# BOC_PWR.net
KiCad netlist of a schematic drawn in Altium Designer
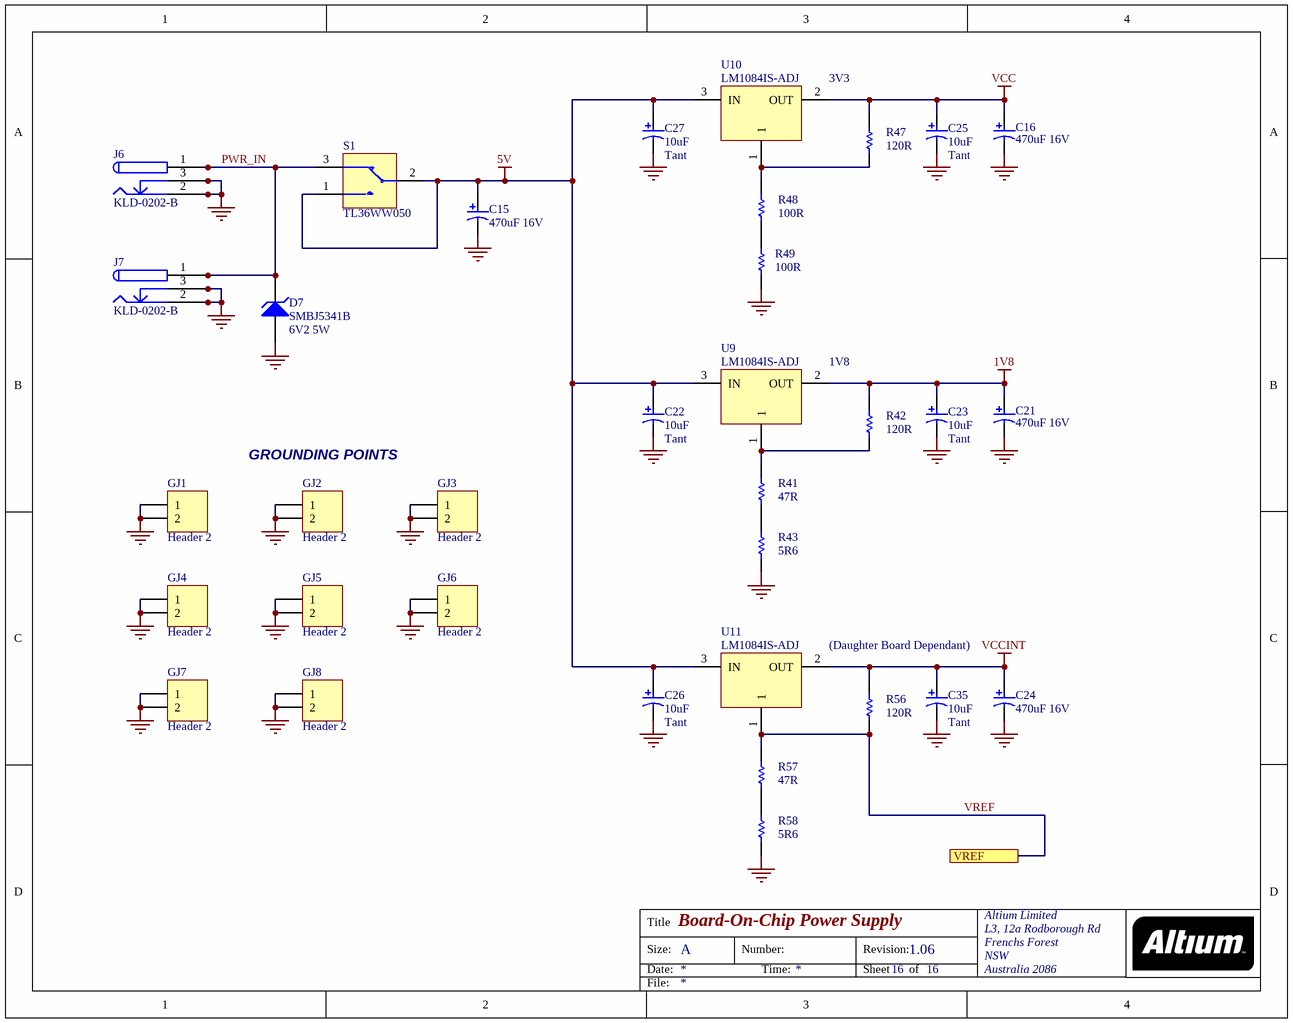
[diagram p0: BOC_PWR.SchDoc]

(export (version "E")
  (design (tool "Eeschema 10.0.6"))
  (components
    (comp (ref "C15")
      (value "470uF 16V")
      (footprint "Altium Nanoboard Project:RB8/3.5")
      (description "Polar Capacitor")
      (libsource (lib "Altium Nanoboard Project") (part "CAP_POLAR"))
    )
    (comp (ref "C16")
      (value "470uF 16V")
      (footprint "Altium Nanoboard Project:RB8/3.5")
      (description "Polar Capacitor")
      (libsource (lib "Altium Nanoboard Project") (part "CAP_POLAR"))
    )
    (comp (ref "C21")
      (value "470uF 16V")
      (footprint "Altium Nanoboard Project:RB8/3.5")
      (description "Polar Capacitor")
      (libsource (lib "Altium Nanoboard Project") (part "CAP_POLAR"))
    )
    (comp (ref "C22")
      (value "10uF")
      (footprint "Altium Nanoboard Project:MCCT-B")
      (description "Polar Capacitor")
      (fields (field (name "CAPACITOR TYPE") "Tant"))
      (libsource (lib "Altium Nanoboard Project") (part "CAP_POLAR"))
    )
    (comp (ref "C23")
      (value "10uF")
      (footprint "Altium Nanoboard Project:MCCT-B")
      (description "Polar Capacitor")
      (fields (field (name "CAPACITOR TYPE") "Tant"))
      (libsource (lib "Altium Nanoboard Project") (part "CAP_POLAR"))
    )
    (comp (ref "C24")
      (value "470uF 16V")
      (footprint "Altium Nanoboard Project:RB8/3.5")
      (description "Polar Capacitor")
      (libsource (lib "Altium Nanoboard Project") (part "CAP_POLAR"))
    )
    (comp (ref "C25")
      (value "10uF")
      (footprint "Altium Nanoboard Project:MCCT-B")
      (description "Polar Capacitor")
      (fields (field (name "CAPACITOR TYPE") "Tant"))
      (libsource (lib "Altium Nanoboard Project") (part "CAP_POLAR"))
    )
    (comp (ref "C26")
      (value "10uF")
      (footprint "Altium Nanoboard Project:MCCT-B")
      (description "Polar Capacitor")
      (fields (field (name "CAPACITOR TYPE") "Tant"))
      (libsource (lib "Altium Nanoboard Project") (part "CAP_POLAR"))
    )
    (comp (ref "C27")
      (value "10uF")
      (footprint "Altium Nanoboard Project:MCCT-B")
      (description "Polar Capacitor")
      (fields (field (name "CAPACITOR TYPE") "Tant"))
      (libsource (lib "Altium Nanoboard Project") (part "CAP_POLAR"))
    )
    (comp (ref "C35")
      (value "10uF")
      (footprint "Altium Nanoboard Project:MCCT-B")
      (description "Polar Capacitor")
      (fields (field (name "CAPACITOR TYPE") "Tant"))
      (libsource (lib "Altium Nanoboard Project") (part "CAP_POLAR"))
    )
    (comp (ref "D7")
      (value "SMBJ5341B")
      (footprint "Altium Nanoboard Project:DO214")
      (description "Zener Diode, 6.2V, 5W")
      (fields (field (name "MANUFACTURER") "Microsemi") (field (name "PART DESCRIPTION") "6V2 5W"))
      (libsource (lib "Altium Nanoboard Project") (part "BZG03C13"))
    )
    (comp (ref "GJ1")
      (value "Header 2")
      (footprint "Altium Nanoboard Project:HDR1X2")
      (description "Header, 2-Pin")
      (fields (field (name "MANUFACTURER") "Generic Components") (field (name "PUBLISHER") "Altium Limited"))
      (libsource (lib "Altium Nanoboard Project") (part "Header 2"))
    )
    (comp (ref "GJ2")
      (value "Header 2")
      (footprint "Altium Nanoboard Project:HDR1X2")
      (description "Header, 2-Pin")
      (fields (field (name "MANUFACTURER") "Generic Components") (field (name "PUBLISHER") "Altium Limited"))
      (libsource (lib "Altium Nanoboard Project") (part "Header 2"))
    )
    (comp (ref "GJ3")
      (value "Header 2")
      (footprint "Altium Nanoboard Project:HDR1X2")
      (description "Header, 2-Pin")
      (fields (field (name "MANUFACTURER") "Generic Components") (field (name "PUBLISHER") "Altium Limited"))
      (libsource (lib "Altium Nanoboard Project") (part "Header 2"))
    )
    (comp (ref "GJ4")
      (value "Header 2")
      (footprint "Altium Nanoboard Project:HDR1X2")
      (description "Header, 2-Pin")
      (fields (field (name "MANUFACTURER") "Generic Components") (field (name "PUBLISHER") "Altium Limited"))
      (libsource (lib "Altium Nanoboard Project") (part "Header 2"))
    )
    (comp (ref "GJ5")
      (value "Header 2")
      (footprint "Altium Nanoboard Project:HDR1X2")
      (description "Header, 2-Pin")
      (fields (field (name "MANUFACTURER") "Generic Components") (field (name "PUBLISHER") "Altium Limited"))
      (libsource (lib "Altium Nanoboard Project") (part "Header 2"))
    )
    (comp (ref "GJ6")
      (value "Header 2")
      (footprint "Altium Nanoboard Project:HDR1X2")
      (description "Header, 2-Pin")
      (fields (field (name "MANUFACTURER") "Generic Components") (field (name "PUBLISHER") "Altium Limited"))
      (libsource (lib "Altium Nanoboard Project") (part "Header 2"))
    )
    (comp (ref "GJ7")
      (value "Header 2")
      (footprint "Altium Nanoboard Project:HDR1X2")
      (description "Header, 2-Pin")
      (fields (field (name "MANUFACTURER") "Generic Components") (field (name "PUBLISHER") "Altium Limited"))
      (libsource (lib "Altium Nanoboard Project") (part "Header 2"))
    )
    (comp (ref "GJ8")
      (value "Header 2")
      (footprint "Altium Nanoboard Project:HDR1X2")
      (description "Header, 2-Pin")
      (fields (field (name "MANUFACTURER") "Generic Components") (field (name "PUBLISHER") "Altium Limited"))
      (libsource (lib "Altium Nanoboard Project") (part "Header 2"))
    )
    (comp (ref "J6")
      (value "KLD-0202-B")
      (footprint "Altium Nanoboard Project:KLD-0202")
      (description "Low Voltage Power Supply Connector")
      (fields (field (name "MANUFACTURER") "Kycon"))
      (libsource (lib "Altium Nanoboard Project") (part "KLD-0202-B"))
    )
    (comp (ref "J7")
      (value "KLD-0202-B")
      (footprint "Altium Nanoboard Project:KLD-0202")
      (description "Low Voltage Power Supply Connector")
      (fields (field (name "MANUFACTURER") "Kycon"))
      (libsource (lib "Altium Nanoboard Project") (part "KLD-0202-B"))
    )
    (comp (ref "R41")
      (value "47R")
      (footprint "Altium Nanoboard Project:CC2012-0805")
      (description "Resistor")
      (libsource (lib "Altium Nanoboard Project") (part "RES"))
    )
    (comp (ref "R42")
      (value "120R")
      (footprint "Altium Nanoboard Project:CC2012-0805")
      (description "Resistor")
      (libsource (lib "Altium Nanoboard Project") (part "RES"))
    )
    (comp (ref "R43")
      (value "5R6")
      (footprint "Altium Nanoboard Project:CC2012-0805")
      (description "Resistor")
      (libsource (lib "Altium Nanoboard Project") (part "RES"))
    )
    (comp (ref "R47")
      (value "120R")
      (footprint "Altium Nanoboard Project:CC2012-0805")
      (description "Resistor")
      (libsource (lib "Altium Nanoboard Project") (part "RES"))
    )
    (comp (ref "R48")
      (value "100R")
      (footprint "Altium Nanoboard Project:CC2012-0805")
      (description "Resistor")
      (libsource (lib "Altium Nanoboard Project") (part "RES"))
    )
    (comp (ref "R49")
      (value "100R")
      (footprint "Altium Nanoboard Project:CC2012-0805")
      (description "Resistor")
      (libsource (lib "Altium Nanoboard Project") (part "RES"))
    )
    (comp (ref "R56")
      (value "120R")
      (footprint "Altium Nanoboard Project:CC2012-0805")
      (description "Resistor")
      (libsource (lib "Altium Nanoboard Project") (part "RES"))
    )
    (comp (ref "R57")
      (value "47R")
      (footprint "Altium Nanoboard Project:CC2012-0805")
      (description "Resistor")
      (libsource (lib "Altium Nanoboard Project") (part "RES"))
    )
    (comp (ref "R58")
      (value "5R6")
      (footprint "Altium Nanoboard Project:CC2012-0805")
      (description "Resistor")
      (libsource (lib "Altium Nanoboard Project") (part "RES"))
    )
    (comp (ref "S1")
      (value "TL36WW050")
      (footprint "Altium Nanoboard Project:TL36WW15050")
      (description "SPDT Subminiature Toggle Switch")
      (libsource (lib "Altium Nanoboard Project") (part "PCB_MOUNT_SWITCH"))
    )
    (comp (ref "U9")
      (value "LM1084IS-ADJ")
      (footprint "Altium Nanoboard Project:TO-263")
      (description "5A Low Dropout Possitive Regulators")
      (libsource (lib "Altium Nanoboard Project") (part "LM1084IS-ADJ"))
    )
    (comp (ref "U10")
      (value "LM1084IS-ADJ")
      (footprint "Altium Nanoboard Project:TO-263")
      (description "5A Low Dropout Possitive Regulators")
      (libsource (lib "Altium Nanoboard Project") (part "LM1084IS-ADJ"))
    )
    (comp (ref "U11")
      (value "LM1084IS-ADJ")
      (footprint "Altium Nanoboard Project:TO-263")
      (description "5A Low Dropout Possitive Regulators")
      (libsource (lib "Altium Nanoboard Project") (part "LM1084IS-ADJ"))
    )
  )
  (nets
    (net (code "1") (name "/PWR_IN") (class "Default")
      (node (ref "D7") (pin "2") (pinfunction "K_2") (pintype "passive"))
      (node (ref "J6") (pin "1") (pintype "power_in"))
      (node (ref "J6") (pin "1A") (pintype "power_in"))
      (node (ref "J6") (pin "1B") (pintype "power_in"))
      (node (ref "J7") (pin "1") (pintype "power_in"))
      (node (ref "J7") (pin "1A") (pintype "power_in"))
      (node (ref "J7") (pin "1B") (pintype "power_in"))
      (node (ref "S1") (pin "3") (pintype "passive"))
    )
    (net (code "2") (name "/VREF") (class "Default")
      (node (ref "R56") (pin "2") (pinfunction "2_2") (pintype "passive"))
      (node (ref "R57") (pin "1") (pinfunction "1_1") (pintype "passive"))
      (node (ref "U11") (pin "1") (pinfunction "1_1") (pintype "passive"))
    )
    (net (code "3") (name "1V8") (class "Default")
      (node (ref "C21") (pin "1") (pinfunction "1_1") (pintype "passive"))
      (node (ref "C23") (pin "1") (pinfunction "1_1") (pintype "passive"))
      (node (ref "R42") (pin "1") (pinfunction "1_1") (pintype "passive"))
      (node (ref "U9") (pin "2") (pinfunction "OUT_2") (pintype "power_in"))
    )
    (net (code "4") (name "5V") (class "Default")
      (node (ref "C15") (pin "1") (pinfunction "1_1") (pintype "passive"))
      (node (ref "C22") (pin "1") (pinfunction "1_1") (pintype "passive"))
      (node (ref "C26") (pin "1") (pinfunction "1_1") (pintype "passive"))
      (node (ref "C27") (pin "1") (pinfunction "1_1") (pintype "passive"))
      (node (ref "S1") (pin "1") (pintype "passive"))
      (node (ref "S1") (pin "2") (pintype "passive"))
      (node (ref "U10") (pin "3") (pinfunction "IN_3") (pintype "power_in"))
      (node (ref "U11") (pin "3") (pinfunction "IN_3") (pintype "power_in"))
      (node (ref "U9") (pin "3") (pinfunction "IN_3") (pintype "power_in"))
    )
    (net (code "5") (name "GND") (class "Default")
      (node (ref "C15") (pin "2") (pinfunction "2_2") (pintype "passive"))
      (node (ref "C16") (pin "2") (pinfunction "2_2") (pintype "passive"))
      (node (ref "C21") (pin "2") (pinfunction "2_2") (pintype "passive"))
      (node (ref "C22") (pin "2") (pinfunction "2_2") (pintype "passive"))
      (node (ref "C23") (pin "2") (pinfunction "2_2") (pintype "passive"))
      (node (ref "C24") (pin "2") (pinfunction "2_2") (pintype "passive"))
      (node (ref "C25") (pin "2") (pinfunction "2_2") (pintype "passive"))
      (node (ref "C26") (pin "2") (pinfunction "2_2") (pintype "passive"))
      (node (ref "C27") (pin "2") (pinfunction "2_2") (pintype "passive"))
      (node (ref "C35") (pin "2") (pinfunction "2_2") (pintype "passive"))
      (node (ref "D7") (pin "1") (pinfunction "A_1") (pintype "passive"))
      (node (ref "GJ1") (pin "1") (pinfunction "1_1") (pintype "passive"))
      (node (ref "GJ1") (pin "2") (pinfunction "2_2") (pintype "passive"))
      (node (ref "GJ2") (pin "1") (pinfunction "1_1") (pintype "passive"))
      (node (ref "GJ2") (pin "2") (pinfunction "2_2") (pintype "passive"))
      (node (ref "GJ3") (pin "1") (pinfunction "1_1") (pintype "passive"))
      (node (ref "GJ3") (pin "2") (pinfunction "2_2") (pintype "passive"))
      (node (ref "GJ4") (pin "1") (pinfunction "1_1") (pintype "passive"))
      (node (ref "GJ4") (pin "2") (pinfunction "2_2") (pintype "passive"))
      (node (ref "GJ5") (pin "1") (pinfunction "1_1") (pintype "passive"))
      (node (ref "GJ5") (pin "2") (pinfunction "2_2") (pintype "passive"))
      (node (ref "GJ6") (pin "1") (pinfunction "1_1") (pintype "passive"))
      (node (ref "GJ6") (pin "2") (pinfunction "2_2") (pintype "passive"))
      (node (ref "GJ7") (pin "1") (pinfunction "1_1") (pintype "passive"))
      (node (ref "GJ7") (pin "2") (pinfunction "2_2") (pintype "passive"))
      (node (ref "GJ8") (pin "1") (pinfunction "1_1") (pintype "passive"))
      (node (ref "GJ8") (pin "2") (pinfunction "2_2") (pintype "passive"))
      (node (ref "J6") (pin "2") (pintype "power_in"))
      (node (ref "J6") (pin "2A") (pintype "power_in"))
      (node (ref "J6") (pin "2B") (pintype "power_in"))
      (node (ref "J6") (pin "3") (pintype "power_in"))
      (node (ref "J6") (pin "3A") (pintype "power_in"))
      (node (ref "J6") (pin "3B") (pintype "power_in"))
      (node (ref "J7") (pin "2") (pintype "power_in"))
      (node (ref "J7") (pin "2A") (pintype "power_in"))
      (node (ref "J7") (pin "2B") (pintype "power_in"))
      (node (ref "J7") (pin "3") (pintype "power_in"))
      (node (ref "J7") (pin "3A") (pintype "power_in"))
      (node (ref "J7") (pin "3B") (pintype "power_in"))
      (node (ref "R43") (pin "2") (pinfunction "2_2") (pintype "passive"))
      (node (ref "R49") (pin "1") (pinfunction "1_1") (pintype "passive"))
      (node (ref "R58") (pin "2") (pinfunction "2_2") (pintype "passive"))
    )
    (net (code "6") (name "Net-(R41-Pad1)") (class "Default")
      (node (ref "R41") (pin "1") (pinfunction "1_1") (pintype "passive"))
      (node (ref "R42") (pin "2") (pinfunction "2_2") (pintype "passive"))
      (node (ref "U9") (pin "1") (pinfunction "1_1") (pintype "passive"))
    )
    (net (code "7") (name "Net-(R41-Pad2)") (class "Default")
      (node (ref "R41") (pin "2") (pinfunction "2_2") (pintype "passive"))
      (node (ref "R43") (pin "1") (pinfunction "1_1") (pintype "passive"))
    )
    (net (code "8") (name "Net-(R47-Pad2)") (class "Default")
      (node (ref "R47") (pin "2") (pinfunction "2_2") (pintype "passive"))
      (node (ref "R48") (pin "1") (pinfunction "1_1") (pintype "passive"))
      (node (ref "U10") (pin "1") (pinfunction "1_1") (pintype "passive"))
    )
    (net (code "9") (name "Net-(R48-Pad2)") (class "Default")
      (node (ref "R48") (pin "2") (pinfunction "2_2") (pintype "passive"))
      (node (ref "R49") (pin "2") (pinfunction "2_2") (pintype "passive"))
    )
    (net (code "10") (name "Net-(R57-Pad2)") (class "Default")
      (node (ref "R57") (pin "2") (pinfunction "2_2") (pintype "passive"))
      (node (ref "R58") (pin "1") (pinfunction "1_1") (pintype "passive"))
    )
    (net (code "11") (name "VCC") (class "Default")
      (node (ref "C16") (pin "1") (pinfunction "1_1") (pintype "passive"))
      (node (ref "C25") (pin "1") (pinfunction "1_1") (pintype "passive"))
      (node (ref "R47") (pin "1") (pinfunction "1_1") (pintype "passive"))
      (node (ref "U10") (pin "2") (pinfunction "OUT_2") (pintype "power_in"))
    )
    (net (code "12") (name "VCCINT") (class "Default")
      (node (ref "C24") (pin "1") (pinfunction "1_1") (pintype "passive"))
      (node (ref "C35") (pin "1") (pinfunction "1_1") (pintype "passive"))
      (node (ref "R56") (pin "1") (pinfunction "1_1") (pintype "passive"))
      (node (ref "U11") (pin "2") (pinfunction "OUT_2") (pintype "power_in"))
    )
  )
)
